# NewPowerandPlaceSCH.net
KiCad netlist of a schematic drawn in Altium Designer
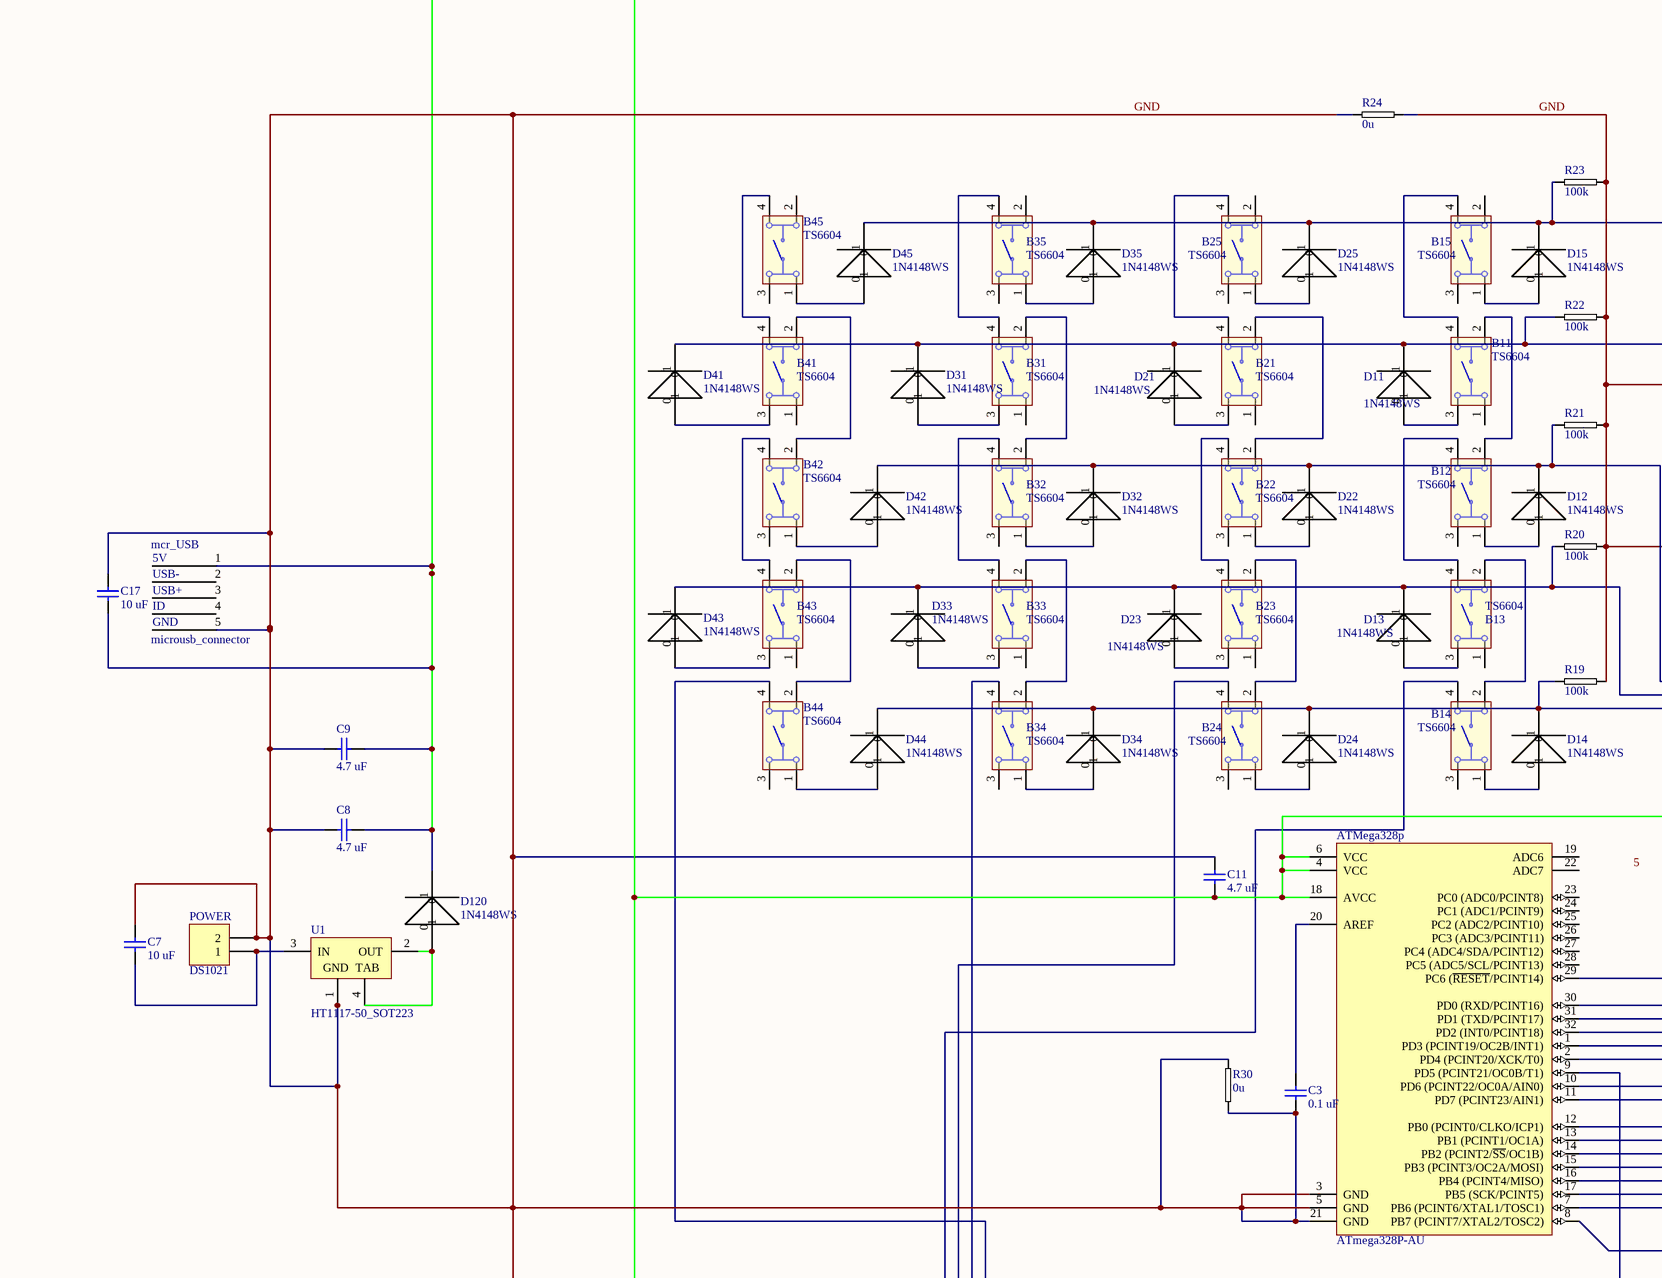
[diagram p0: NewPowerandPlaceSCH.SchDoc, top left]
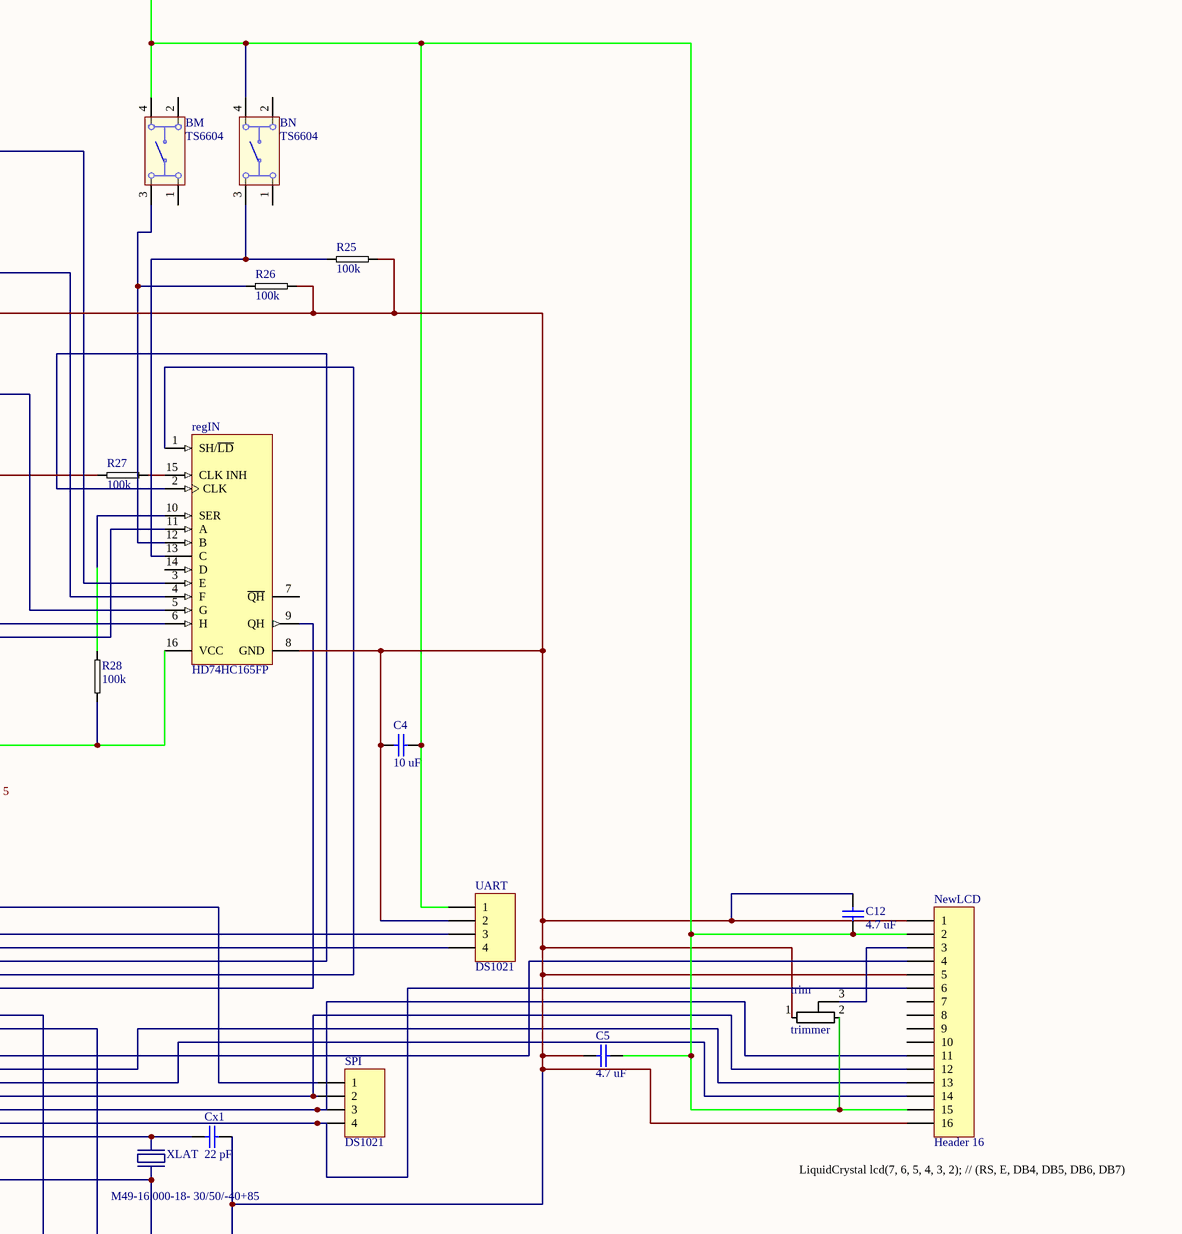
[diagram p1: NewPowerandPlaceSCH.SchDoc, top right]
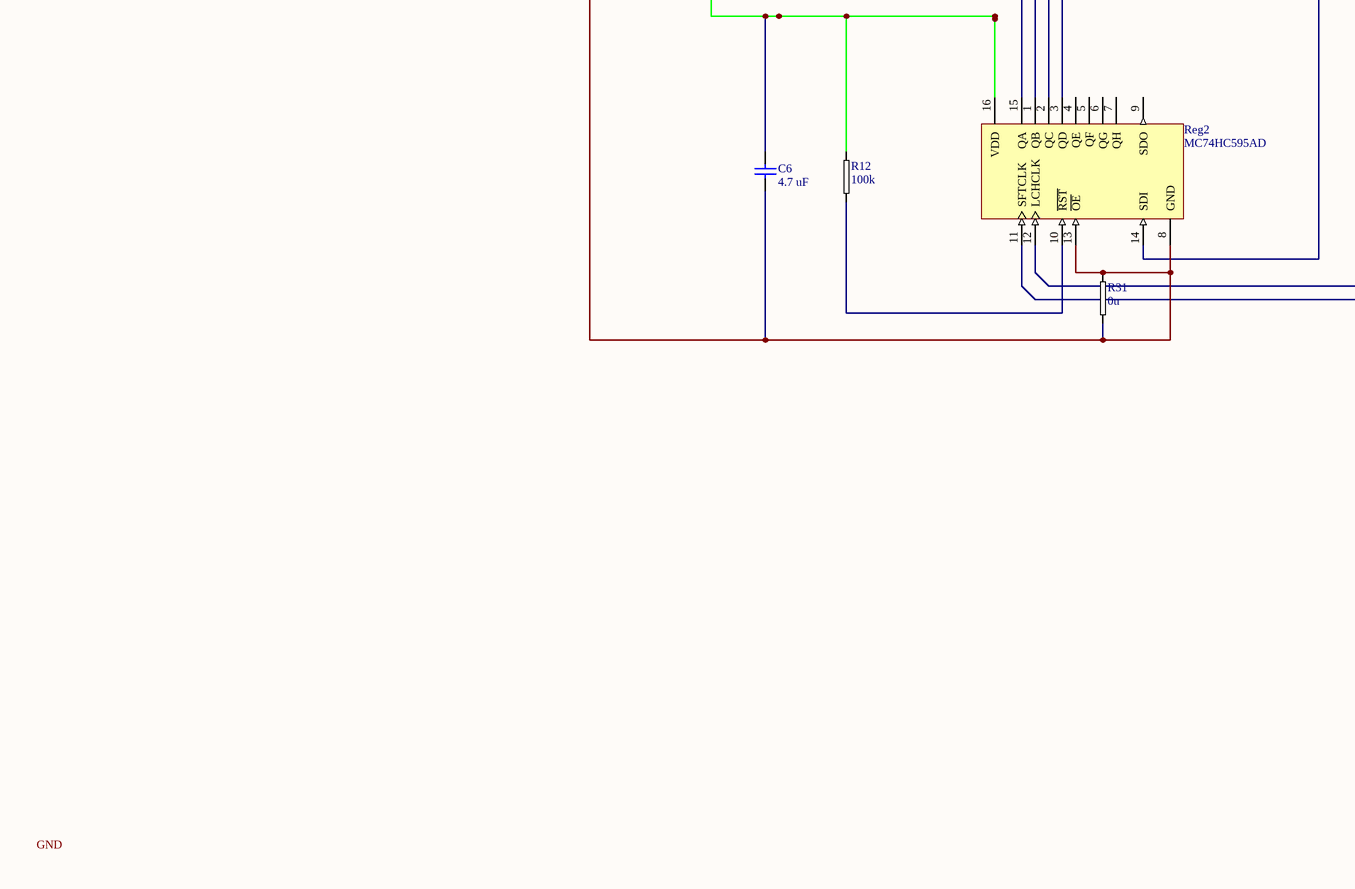
[diagram p2: NewPowerandPlaceSCH.SchDoc, bottom left]
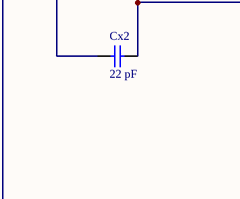
[diagram p3: NewPowerandPlaceSCH.SchDoc, bottom right]

(export (version "E")
  (design (tool "Eeschema 10.0.6"))
  (components
    (comp (ref "ATMega328p")
      (value "ATmega328P-AU")
      (footprint "32A_N")
      (libsource (lib "Atmel Microcontroller megaAVR") (part "ATmega328P-AU"))
    )
    (comp (ref "B11")
      (value "TS6604")
      (footprint "430182070816")
      (description "WS-TASV SMD Tact Switch 6X6 mm")
      (fields (field (name "PARTNUMBER") "430182070816"))
      (libsource (lib "WS-TASV SMD Tact Switch 6X6 mm") (part "430182070816"))
    )
    (comp (ref "B12")
      (value "TS6604")
      (footprint "430182070816")
      (description "WS-TASV SMD Tact Switch 6X6 mm")
      (fields (field (name "PARTNUMBER") "430182070816"))
      (libsource (lib "WS-TASV SMD Tact Switch 6X6 mm") (part "430182070816"))
    )
    (comp (ref "B13")
      (value "TS6604")
      (footprint "430182070816")
      (description "WS-TASV SMD Tact Switch 6X6 mm")
      (fields (field (name "PARTNUMBER") "430182070816"))
      (libsource (lib "WS-TASV SMD Tact Switch 6X6 mm") (part "430182070816"))
    )
    (comp (ref "B14")
      (value "TS6604")
      (footprint "430182070816")
      (description "WS-TASV SMD Tact Switch 6X6 mm")
      (fields (field (name "PARTNUMBER") "430182070816"))
      (libsource (lib "WS-TASV SMD Tact Switch 6X6 mm") (part "430182070816"))
    )
    (comp (ref "B15")
      (value "TS6604")
      (footprint "430182070816")
      (description "WS-TASV SMD Tact Switch 6X6 mm")
      (fields (field (name "PARTNUMBER") "430182070816"))
      (libsource (lib "WS-TASV SMD Tact Switch 6X6 mm") (part "430182070816"))
    )
    (comp (ref "B21")
      (value "TS6604")
      (footprint "430182070816")
      (description "WS-TASV SMD Tact Switch 6X6 mm")
      (fields (field (name "PARTNUMBER") "430182070816"))
      (libsource (lib "WS-TASV SMD Tact Switch 6X6 mm") (part "430182070816"))
    )
    (comp (ref "B22")
      (value "TS6604")
      (footprint "430182070816")
      (description "WS-TASV SMD Tact Switch 6X6 mm")
      (fields (field (name "PARTNUMBER") "430182070816"))
      (libsource (lib "WS-TASV SMD Tact Switch 6X6 mm") (part "430182070816"))
    )
    (comp (ref "B23")
      (value "TS6604")
      (footprint "430182070816")
      (description "WS-TASV SMD Tact Switch 6X6 mm")
      (fields (field (name "PARTNUMBER") "430182070816"))
      (libsource (lib "WS-TASV SMD Tact Switch 6X6 mm") (part "430182070816"))
    )
    (comp (ref "B24")
      (value "TS6604")
      (footprint "430182070816")
      (description "WS-TASV SMD Tact Switch 6X6 mm")
      (fields (field (name "PARTNUMBER") "430182070816"))
      (libsource (lib "WS-TASV SMD Tact Switch 6X6 mm") (part "430182070816"))
    )
    (comp (ref "B25")
      (value "TS6604")
      (footprint "430182070816")
      (description "WS-TASV SMD Tact Switch 6X6 mm")
      (fields (field (name "PARTNUMBER") "430182070816"))
      (libsource (lib "WS-TASV SMD Tact Switch 6X6 mm") (part "430182070816"))
    )
    (comp (ref "B31")
      (value "TS6604")
      (footprint "430182070816")
      (description "WS-TASV SMD Tact Switch 6X6 mm")
      (fields (field (name "PARTNUMBER") "430182070816"))
      (libsource (lib "WS-TASV SMD Tact Switch 6X6 mm") (part "430182070816"))
    )
    (comp (ref "B32")
      (value "TS6604")
      (footprint "430182070816")
      (description "WS-TASV SMD Tact Switch 6X6 mm")
      (fields (field (name "PARTNUMBER") "430182070816"))
      (libsource (lib "WS-TASV SMD Tact Switch 6X6 mm") (part "430182070816"))
    )
    (comp (ref "B33")
      (value "TS6604")
      (footprint "430182070816")
      (description "WS-TASV SMD Tact Switch 6X6 mm")
      (fields (field (name "PARTNUMBER") "430182070816"))
      (libsource (lib "WS-TASV SMD Tact Switch 6X6 mm") (part "430182070816"))
    )
    (comp (ref "B34")
      (value "TS6604")
      (footprint "430182070816")
      (description "WS-TASV SMD Tact Switch 6X6 mm")
      (fields (field (name "PARTNUMBER") "430182070816"))
      (libsource (lib "WS-TASV SMD Tact Switch 6X6 mm") (part "430182070816"))
    )
    (comp (ref "B35")
      (value "TS6604")
      (footprint "430182070816")
      (description "WS-TASV SMD Tact Switch 6X6 mm")
      (fields (field (name "PARTNUMBER") "430182070816"))
      (libsource (lib "WS-TASV SMD Tact Switch 6X6 mm") (part "430182070816"))
    )
    (comp (ref "B41")
      (value "TS6604")
      (footprint "430182070816")
      (description "WS-TASV SMD Tact Switch 6X6 mm")
      (fields (field (name "PARTNUMBER") "430182070816"))
      (libsource (lib "WS-TASV SMD Tact Switch 6X6 mm") (part "430182070816"))
    )
    (comp (ref "B42")
      (value "TS6604")
      (footprint "430182070816")
      (description "WS-TASV SMD Tact Switch 6X6 mm")
      (fields (field (name "PARTNUMBER") "430182070816"))
      (libsource (lib "WS-TASV SMD Tact Switch 6X6 mm") (part "430182070816"))
    )
    (comp (ref "B43")
      (value "TS6604")
      (footprint "430182070816")
      (description "WS-TASV SMD Tact Switch 6X6 mm")
      (fields (field (name "PARTNUMBER") "430182070816"))
      (libsource (lib "WS-TASV SMD Tact Switch 6X6 mm") (part "430182070816"))
    )
    (comp (ref "B44")
      (value "TS6604")
      (footprint "430182070816")
      (description "WS-TASV SMD Tact Switch 6X6 mm")
      (fields (field (name "PARTNUMBER") "430182070816"))
      (libsource (lib "WS-TASV SMD Tact Switch 6X6 mm") (part "430182070816"))
    )
    (comp (ref "B45")
      (value "TS6604")
      (footprint "430182070816")
      (description "WS-TASV SMD Tact Switch 6X6 mm")
      (fields (field (name "PARTNUMBER") "430182070816"))
      (libsource (lib "WS-TASV SMD Tact Switch 6X6 mm") (part "430182070816"))
    )
    (comp (ref "BM")
      (value "TS6604")
      (footprint "430182070816")
      (description "WS-TASV SMD Tact Switch 6X6 mm")
      (fields (field (name "PARTNUMBER") "430182070816"))
      (libsource (lib "WS-TASV SMD Tact Switch 6X6 mm") (part "430182070816"))
    )
    (comp (ref "BN")
      (value "TS6604")
      (footprint "430182070816")
      (description "WS-TASV SMD Tact Switch 6X6 mm")
      (fields (field (name "PARTNUMBER") "430182070816"))
      (libsource (lib "WS-TASV SMD Tact Switch 6X6 mm") (part "430182070816"))
    )
    (comp (ref "C3")
      (value "0.1 uF")
      (footprint "0805")
      (description "Ceramic Chip Capacitor - Standard")
      (fields (field (name "PUBLISHER") "Altium Limited"))
      (libsource (lib "KEMET Chip Capacitor") (part "C0805"))
    )
    (comp (ref "C11")
      (value "4.7 uF")
      (footprint "0805")
      (description "Ceramic Chip Capacitor - Standard")
      (fields (field (name "PUBLISHER") "Altium Limited"))
      (libsource (lib "KEMET Chip Capacitor") (part "C0805"))
    )
    (comp (ref "C12")
      (value "4.7 uF")
      (footprint "0805")
      (description "Ceramic Chip Capacitor - Standard")
      (fields (field (name "PUBLISHER") "Altium Limited"))
      (libsource (lib "KEMET Chip Capacitor") (part "C0805"))
    )
    (comp (ref "C17")
      (value "10 uF")
      (footprint "0805")
      (description "Ceramic Chip Capacitor - Standard")
      (fields (field (name "PUBLISHER") "Altium Limited"))
      (libsource (lib "KEMET Chip Capacitor") (part "C0805"))
    )
    (comp (ref "D11") (value "1N4148WS") (footprint "abak:sod323") (libsource (lib "abak") (part "SOD323")))
    (comp (ref "D12") (value "1N4148WS") (footprint "abak:sod323") (libsource (lib "abak") (part "SOD323")))
    (comp (ref "D13") (value "1N4148WS") (footprint "abak:sod323") (libsource (lib "abak") (part "SOD323")))
    (comp (ref "D14") (value "1N4148WS") (footprint "abak:sod323") (libsource (lib "abak") (part "SOD323")))
    (comp (ref "D15") (value "1N4148WS") (footprint "abak:sod323") (libsource (lib "abak") (part "SOD323")))
    (comp (ref "D21") (value "1N4148WS") (footprint "abak:sod323") (libsource (lib "abak") (part "SOD323")))
    (comp (ref "D22") (value "1N4148WS") (footprint "abak:sod323") (libsource (lib "abak") (part "SOD323")))
    (comp (ref "D23") (value "1N4148WS") (footprint "abak:sod323") (libsource (lib "abak") (part "SOD323")))
    (comp (ref "D24") (value "1N4148WS") (footprint "abak:sod323") (libsource (lib "abak") (part "SOD323")))
    (comp (ref "D25") (value "1N4148WS") (footprint "abak:sod323") (libsource (lib "abak") (part "SOD323")))
    (comp (ref "D31") (value "1N4148WS") (footprint "abak:sod323") (libsource (lib "abak") (part "SOD323")))
    (comp (ref "D32") (value "1N4148WS") (footprint "abak:sod323") (libsource (lib "abak") (part "SOD323")))
    (comp (ref "D33") (value "1N4148WS") (footprint "abak:sod323") (libsource (lib "abak") (part "SOD323")))
    (comp (ref "D34") (value "1N4148WS") (footprint "abak:sod323") (libsource (lib "abak") (part "SOD323")))
    (comp (ref "D35") (value "1N4148WS") (footprint "abak:sod323") (libsource (lib "abak") (part "SOD323")))
    (comp (ref "D41") (value "1N4148WS") (footprint "abak:sod323") (libsource (lib "abak") (part "SOD323")))
    (comp (ref "D42") (value "1N4148WS") (footprint "abak:sod323") (libsource (lib "abak") (part "SOD323")))
    (comp (ref "D43") (value "1N4148WS") (footprint "abak:sod323") (libsource (lib "abak") (part "SOD323")))
    (comp (ref "D44") (value "1N4148WS") (footprint "abak:sod323") (libsource (lib "abak") (part "SOD323")))
    (comp (ref "D45") (value "1N4148WS") (footprint "abak:sod323") (libsource (lib "abak") (part "SOD323")))
    (comp (ref "D120") (value "1N4148WS") (footprint "abak:sod323") (libsource (lib "abak") (part "SOD323")))
    (comp (ref "mcr_USB")
      (value "microusb_connector")
      (footprint "USB_connector_2")
      (libsource (lib "abak") (part "microusb_connector"))
    )
    (comp (ref "NewLCD")
      (value "Header 16")
      (footprint "HDR1X16")
      (description "Header, 16-Pin")
      (fields (field (name "PUBLISHER") "Altium Limited"))
      (libsource (lib "Miscellaneous Connectors") (part "Header 16"))
    )
    (comp (ref "POWER")
      (value "DS1021")
      (footprint "HDR1X2")
      (description "Header, 2-Pin")
      (fields (field (name "PUBLISHER") "Altium Limited"))
      (libsource (lib "Miscellaneous Connectors") (part "Header 2"))
    )
    (comp (ref "R12") (value "100k") (footprint "res_0805") (libsource (lib "") (part "res_0805_1")))
    (comp (ref "R19") (value "100k") (footprint "res_0805") (libsource (lib "res") (part "res_0805")))
    (comp (ref "R20") (value "100k") (footprint "res_0805") (libsource (lib "res") (part "res_0805")))
    (comp (ref "R21") (value "100k") (footprint "res_0805") (libsource (lib "res") (part "res_0805")))
    (comp (ref "R22") (value "100k") (footprint "res_0805") (libsource (lib "res") (part "res_0805")))
    (comp (ref "R23") (value "100k") (footprint "res_0805") (libsource (lib "res") (part "res_0805")))
    (comp (ref "R24") (value "0u") (footprint "res_0805") (libsource (lib "res") (part "res_0805")))
    (comp (ref "R25") (value "100k") (footprint "res_0805") (libsource (lib "res") (part "res_0805")))
    (comp (ref "R26") (value "100k") (footprint "res_0805") (libsource (lib "res") (part "res_0805")))
    (comp (ref "R27") (value "100k") (footprint "res_0805") (libsource (lib "res") (part "res_0805")))
    (comp (ref "R28") (value "100k") (footprint "res_0805") (libsource (lib "") (part "res_0805_1")))
    (comp (ref "R30") (value "0u") (footprint "res_0805") (libsource (lib "") (part "res_0805_1")))
    (comp (ref "R31") (value "0u") (footprint "res_0805") (libsource (lib "") (part "res_0805_1")))
    (comp (ref "Reg2")
      (value "MC74HC595AD")
      (footprint "751B-05_N")
      (description "8-Bit Serial-Input/Serial or Prallel-Output Shift Register with Latched 3-State Outputs")
      (fields (field (name "PUBLISHER") "Altium Limited"))
      (libsource (lib "ON Semi Logic Register") (part "MC74HC595AD"))
    )
    (comp (ref "regIN")
      (value "HD74HC165FP")
      (footprint "PRSP0016DH-B_N")
      (description "Parallel-Load 8-bit Shift Register")
      (fields (field (name "PUBLISHER") "Altium Limited"))
      (libsource (lib "Renesas Logic") (part "HD74HC165FP"))
    )
    (comp (ref "SPI")
      (value "DS1021")
      (footprint "HDR1X4")
      (description "Header, 4-Pin")
      (fields (field (name "PUBLISHER") "Altium Limited"))
      (libsource (lib "Miscellaneous Connectors") (part "Header 4"))
    )
    (comp (ref "trim")
      (value "trimmer")
      (footprint "trimmer_place")
      (libsource (lib "abak") (part "trimmer"))
    )
    (comp (ref "U1")
      (value "HT1117-50_SOT223")
      (footprint "SOT223_N")
      (description "5.0V, 1A General Purpose LDO")
      (libsource (lib "Holtek Semiconductor Power Management") (part "HT1117-50_SOT223"))
    )
    (comp (ref "UART")
      (value "DS1021")
      (footprint "HDR1X4")
      (description "Header, 4-Pin")
      (fields (field (name "PUBLISHER") "Altium Limited"))
      (libsource (lib "Miscellaneous Connectors") (part "Header 4"))
    )
    (comp (ref "XLAT")
      (value "M49-16.000-18- 30/50/-40+85")
      (footprint "cristal")
      (libsource (lib "abak") (part "cristal_smd"))
    )
    (comp (ref "С4")
      (value "10 uF")
      (footprint "0805")
      (description "Ceramic Chip Capacitor - Standard")
      (fields (field (name "PUBLISHER") "Altium Limited"))
      (libsource (lib "KEMET Chip Capacitor") (part "C0805"))
    )
    (comp (ref "С5")
      (value "4.7 uF")
      (footprint "0805")
      (description "Ceramic Chip Capacitor - Standard")
      (fields (field (name "PUBLISHER") "Altium Limited"))
      (libsource (lib "KEMET Chip Capacitor") (part "C0805"))
    )
    (comp (ref "С6")
      (value "4.7 uF")
      (footprint "0805")
      (description "Ceramic Chip Capacitor - Standard")
      (fields (field (name "PUBLISHER") "Altium Limited"))
      (libsource (lib "KEMET Chip Capacitor") (part "C0805"))
    )
    (comp (ref "С7")
      (value "10 uF")
      (footprint "0805")
      (description "Ceramic Chip Capacitor - Standard")
      (fields (field (name "PUBLISHER") "Altium Limited"))
      (libsource (lib "KEMET Chip Capacitor") (part "C0805"))
    )
    (comp (ref "С8")
      (value "4.7 uF")
      (footprint "0805")
      (description "Ceramic Chip Capacitor - Standard")
      (fields (field (name "PUBLISHER") "Altium Limited"))
      (libsource (lib "KEMET Chip Capacitor") (part "C0805"))
    )
    (comp (ref "С9")
      (value "4.7 uF")
      (footprint "0805")
      (description "Ceramic Chip Capacitor - Standard")
      (fields (field (name "PUBLISHER") "Altium Limited"))
      (libsource (lib "KEMET Chip Capacitor") (part "C0805"))
    )
    (comp (ref "Сx1")
      (value "22 pF")
      (footprint "res_0805")
      (description "Ceramic Chip Capacitor - Standard")
      (fields (field (name "PUBLISHER") "Altium Limited"))
      (libsource (lib "") (part "C0805_1"))
    )
    (comp (ref "Сx2")
      (value "22 pF")
      (footprint "res_0805")
      (description "Ceramic Chip Capacitor - Standard")
      (fields (field (name "PUBLISHER") "Altium Limited"))
      (libsource (lib "") (part "C0805_1"))
    )
  )
  (nets
    (net (code "2") (name "/GND") (class "Default")
      (node (ref "ATMega328p") (pin "21") (pinfunction "GND_21") (pintype "power_in"))
      (node (ref "ATMega328p") (pin "3") (pinfunction "GND_3") (pintype "power_in"))
      (node (ref "ATMega328p") (pin "5") (pinfunction "GND_5") (pintype "power_in"))
      (node (ref "C11") (pin "1") (pinfunction "1_1") (pintype "passive"))
      (node (ref "C12") (pin "2") (pinfunction "2_2") (pintype "passive"))
      (node (ref "C17") (pin "1") (pinfunction "1_1") (pintype "passive"))
      (node (ref "C3") (pin "2") (pinfunction "2_2") (pintype "passive"))
      (node (ref "NewLCD") (pin "1") (pinfunction "1_1") (pintype "passive"))
      (node (ref "NewLCD") (pin "16") (pinfunction "16_16") (pintype "passive"))
      (node (ref "NewLCD") (pin "5") (pinfunction "5_5") (pintype "passive"))
      (node (ref "POWER") (pin "2") (pinfunction "2_2") (pintype "passive"))
      (node (ref "R19") (pin "1") (pintype "passive"))
      (node (ref "R20") (pin "1") (pintype "passive"))
      (node (ref "R21") (pin "1") (pintype "passive"))
      (node (ref "R22") (pin "1") (pintype "passive"))
      (node (ref "R23") (pin "1") (pintype "passive"))
      (node (ref "R24") (pin "0") (pintype "passive"))
      (node (ref "R24") (pin "1") (pintype "passive"))
      (node (ref "R25") (pin "1") (pintype "passive"))
      (node (ref "R26") (pin "1") (pintype "passive"))
      (node (ref "R27") (pin "0") (pintype "passive"))
      (node (ref "R30") (pin "0") (pintype "passive"))
      (node (ref "R30") (pin "1") (pintype "passive"))
      (node (ref "R31") (pin "0") (pintype "passive"))
      (node (ref "R31") (pin "1") (pintype "passive"))
      (node (ref "Reg2") (pin "13") (pinfunction "~{OE}_13") (pintype "input"))
      (node (ref "Reg2") (pin "8") (pinfunction "GND_8") (pintype "power_in"))
      (node (ref "U1") (pin "1") (pinfunction "GND_1") (pintype "power_in"))
      (node (ref "UART") (pin "2") (pinfunction "2_2") (pintype "passive"))
      (node (ref "mcr_USB") (pin "5") (pintype "passive"))
      (node (ref "regIN") (pin "8") (pinfunction "GND_8") (pintype "power_in"))
      (node (ref "trim") (pin "1") (pintype "passive"))
      (node (ref "С4") (pin "1") (pinfunction "1_1") (pintype "passive"))
      (node (ref "С5") (pin "1") (pinfunction "1_1") (pintype "passive"))
      (node (ref "С6") (pin "2") (pinfunction "2_2") (pintype "passive"))
      (node (ref "С7") (pin "1") (pinfunction "1_1") (pintype "passive"))
      (node (ref "С8") (pin "1") (pinfunction "1_1") (pintype "passive"))
      (node (ref "С9") (pin "1") (pinfunction "1_1") (pintype "passive"))
      (node (ref "Сx1") (pin "1") (pinfunction "2_1") (pintype "passive"))
      (node (ref "Сx2") (pin "1") (pinfunction "2_1") (pintype "passive"))
    )
    (net (code "3") (name "Net-(ATMega328p-AREF)") (class "Default")
      (node (ref "ATMega328p") (pin "20") (pinfunction "AREF_20") (pintype "passive"))
      (node (ref "C3") (pin "1") (pinfunction "1_1") (pintype "passive"))
    )
    (net (code "4") (name "Net-(ATMega328p-AVCC)") (class "Default")
      (node (ref "ATMega328p") (pin "18") (pinfunction "AVCC_18") (pintype "power_in"))
      (node (ref "ATMega328p") (pin "4") (pinfunction "VCC_4") (pintype "power_in"))
      (node (ref "ATMega328p") (pin "6") (pinfunction "VCC_6") (pintype "power_in"))
      (node (ref "BM") (pin "4") (pinfunction "4_4") (pintype "passive"))
      (node (ref "BN") (pin "4") (pinfunction "4_4") (pintype "passive"))
      (node (ref "C11") (pin "2") (pinfunction "2_2") (pintype "passive"))
      (node (ref "C12") (pin "1") (pinfunction "1_1") (pintype "passive"))
      (node (ref "C17") (pin "2") (pinfunction "2_2") (pintype "passive"))
      (node (ref "D120") (pin "1") (pinfunction "1_1") (pintype "passive"))
      (node (ref "NewLCD") (pin "15") (pinfunction "15_15") (pintype "passive"))
      (node (ref "NewLCD") (pin "2") (pinfunction "2_2") (pintype "passive"))
      (node (ref "R12") (pin "1") (pintype "passive"))
      (node (ref "R28") (pin "0") (pintype "passive"))
      (node (ref "Reg2") (pin "16") (pinfunction "VDD_16") (pintype "power_in"))
      (node (ref "UART") (pin "1") (pinfunction "1_1") (pintype "passive"))
      (node (ref "mcr_USB") (pin "1") (pintype "passive"))
      (node (ref "regIN") (pin "16") (pinfunction "VCC_16") (pintype "power_in"))
      (node (ref "trim") (pin "2") (pintype "passive"))
      (node (ref "С4") (pin "2") (pinfunction "2_2") (pintype "passive"))
      (node (ref "С5") (pin "2") (pinfunction "2_2") (pintype "passive"))
      (node (ref "С6") (pin "1") (pinfunction "1_1") (pintype "passive"))
      (node (ref "С8") (pin "2") (pinfunction "2_2") (pintype "passive"))
      (node (ref "С9") (pin "2") (pinfunction "2_2") (pintype "passive"))
    )
    (net (code "5") (name "Net-(ATMega328p-PB0_(PCINT0{slash}CLKO{slash}ICP1))") (class "Default")
      (node (ref "ATMega328p") (pin "12") (pinfunction "PB0_(PCINT0/CLKO/ICP1)_12") (pintype "bidirectional"))
      (node (ref "NewLCD") (pin "4") (pinfunction "4_4") (pintype "passive"))
    )
    (net (code "6") (name "Net-(ATMega328p-PB1_(PCINT1{slash}OC1A))") (class "Default")
      (node (ref "ATMega328p") (pin "13") (pinfunction "PB1_(PCINT1/OC1A)_13") (pintype "bidirectional"))
      (node (ref "NewLCD") (pin "13") (pinfunction "13_13") (pintype "passive"))
    )
    (net (code "7") (name "Net-(ATMega328p-PB2_(PCINT2{slash}~{SS}{slash}OC1B))") (class "Default")
      (node (ref "ATMega328p") (pin "14") (pinfunction "PB2_(PCINT2/~{SS}/OC1B)_14") (pintype "bidirectional"))
      (node (ref "NewLCD") (pin "14") (pinfunction "14_14") (pintype "passive"))
    )
    (net (code "8") (name "Net-(ATMega328p-PB3_(PCINT3{slash}OC2A{slash}MOSI))") (class "Default")
      (node (ref "ATMega328p") (pin "15") (pinfunction "PB3_(PCINT3/OC2A/MOSI)_15") (pintype "bidirectional"))
      (node (ref "NewLCD") (pin "12") (pinfunction "12_12") (pintype "passive"))
      (node (ref "SPI") (pin "2") (pinfunction "2_2") (pintype "passive"))
    )
    (net (code "9") (name "Net-(ATMega328p-PB4_(PCINT4{slash}MISO))") (class "Default")
      (node (ref "ATMega328p") (pin "16") (pinfunction "PB4_(PCINT4/MISO)_16") (pintype "bidirectional"))
      (node (ref "NewLCD") (pin "11") (pinfunction "11_11") (pintype "passive"))
      (node (ref "SPI") (pin "3") (pinfunction "3_3") (pintype "passive"))
    )
    (net (code "10") (name "Net-(ATMega328p-PB5_(SCK{slash}PCINT5))") (class "Default")
      (node (ref "ATMega328p") (pin "17") (pinfunction "PB5_(SCK/PCINT5)_17") (pintype "bidirectional"))
      (node (ref "NewLCD") (pin "6") (pinfunction "6_6") (pintype "passive"))
      (node (ref "SPI") (pin "4") (pinfunction "4_4") (pintype "passive"))
    )
    (net (code "11") (name "Net-(ATMega328p-PB6_(PCINT6{slash}XTAL1{slash}TOSC1))") (class "Default")
      (node (ref "ATMega328p") (pin "7") (pinfunction "PB6_(PCINT6/XTAL1/TOSC1)_7") (pintype "bidirectional"))
      (node (ref "XLAT") (pin "1") (pintype "passive"))
      (node (ref "Сx1") (pin "0") (pinfunction "1_0") (pintype "passive"))
    )
    (net (code "12") (name "Net-(ATMega328p-PB7_(PCINT7{slash}XTAL2{slash}TOSC2))") (class "Default")
      (node (ref "ATMega328p") (pin "8") (pinfunction "PB7_(PCINT7/XTAL2/TOSC2)_8") (pintype "bidirectional"))
      (node (ref "XLAT") (pin "0") (pintype "passive"))
      (node (ref "Сx2") (pin "0") (pinfunction "1_0") (pintype "passive"))
    )
    (net (code "13") (name "Net-(ATMega328p-PC6_(~{RESET}{slash}PCINT14))") (class "Default")
      (node (ref "ATMega328p") (pin "29") (pinfunction "PC6_(~{RESET}/PCINT14)_29") (pintype "bidirectional"))
      (node (ref "SPI") (pin "1") (pinfunction "1_1") (pintype "passive"))
    )
    (net (code "14") (name "Net-(ATMega328p-PD0_(RXD{slash}PCINT16))") (class "Default")
      (node (ref "ATMega328p") (pin "30") (pinfunction "PD0_(RXD/PCINT16)_30") (pintype "bidirectional"))
      (node (ref "UART") (pin "3") (pinfunction "3_3") (pintype "passive"))
    )
    (net (code "15") (name "Net-(ATMega328p-PD1_(TXD{slash}PCINT17))") (class "Default")
      (node (ref "ATMega328p") (pin "31") (pinfunction "PD1_(TXD/PCINT17)_31") (pintype "bidirectional"))
      (node (ref "UART") (pin "4") (pinfunction "4_4") (pintype "passive"))
    )
    (net (code "16") (name "Net-(ATMega328p-PD2_(INT0{slash}PCINT18))") (class "Default")
      (node (ref "ATMega328p") (pin "32") (pinfunction "PD2_(INT0/PCINT18)_32") (pintype "bidirectional"))
      (node (ref "regIN") (pin "2") (pinfunction "CLK_2") (pintype "input"))
    )
    (net (code "17") (name "Net-(ATMega328p-PD3_(PCINT19{slash}OC2B{slash}INT1))") (class "Default")
      (node (ref "ATMega328p") (pin "1") (pinfunction "PD3_(PCINT19/OC2B/INT1)_1") (pintype "bidirectional"))
      (node (ref "regIN") (pin "1") (pinfunction "SH/~{LD}_1") (pintype "input"))
    )
    (net (code "18") (name "Net-(ATMega328p-PD4_(PCINT20{slash}XCK{slash}T0))") (class "Default")
      (node (ref "ATMega328p") (pin "2") (pinfunction "PD4_(PCINT20/XCK/T0)_2") (pintype "bidirectional"))
      (node (ref "regIN") (pin "9") (pinfunction "QH_9") (pintype "output"))
    )
    (net (code "19") (name "Net-(ATMega328p-PD5_(PCINT21{slash}OC0B{slash}T1))") (class "Default")
      (node (ref "ATMega328p") (pin "9") (pinfunction "PD5_(PCINT21/OC0B/T1)_9") (pintype "bidirectional"))
      (node (ref "Reg2") (pin "14") (pinfunction "SDI_14") (pintype "input"))
    )
    (net (code "20") (name "Net-(ATMega328p-PD6_(PCINT22{slash}OC0A{slash}AIN0))") (class "Default")
      (node (ref "ATMega328p") (pin "10") (pinfunction "PD6_(PCINT22/OC0A/AIN0)_10") (pintype "bidirectional"))
      (node (ref "Reg2") (pin "12") (pinfunction "LCHCLK_12") (pintype "input"))
    )
    (net (code "21") (name "Net-(ATMega328p-PD7_(PCINT23{slash}AIN1))") (class "Default")
      (node (ref "ATMega328p") (pin "11") (pinfunction "PD7_(PCINT23/AIN1)_11") (pintype "bidirectional"))
      (node (ref "Reg2") (pin "11") (pinfunction "SFTCLK_11") (pintype "input"))
    )
    (net (code "22") (name "Net-(B11-Pad2)") (class "Default")
      (node (ref "B11") (pin "2") (pinfunction "2_2") (pintype "passive"))
      (node (ref "B12") (pin "2") (pinfunction "2_2") (pintype "passive"))
    )
    (net (code "23") (name "Net-(B11-Pad3)") (class "Default")
      (node (ref "B11") (pin "3") (pinfunction "3_3") (pintype "passive"))
      (node (ref "D11") (pin "0") (pinfunction "0_0") (pintype "passive"))
    )
    (net (code "24") (name "Net-(B11-Pad4)") (class "Default")
      (node (ref "B11") (pin "4") (pinfunction "4_4") (pintype "passive"))
      (node (ref "B15") (pin "4") (pinfunction "4_4") (pintype "passive"))
    )
    (net (code "25") (name "Net-(B12-Pad1)") (class "Default")
      (node (ref "B12") (pin "1") (pinfunction "1_1") (pintype "passive"))
      (node (ref "D12") (pin "0") (pinfunction "0_0") (pintype "passive"))
    )
    (net (code "26") (name "Net-(B12-Pad4)") (class "Default")
      (node (ref "B12") (pin "4") (pinfunction "4_4") (pintype "passive"))
      (node (ref "B13") (pin "4") (pinfunction "4_4") (pintype "passive"))
    )
    (net (code "27") (name "Net-(B13-Pad2)") (class "Default")
      (node (ref "B13") (pin "2") (pinfunction "2_2") (pintype "passive"))
      (node (ref "B14") (pin "2") (pinfunction "2_2") (pintype "passive"))
    )
    (net (code "28") (name "Net-(B13-Pad3)") (class "Default")
      (node (ref "B13") (pin "3") (pinfunction "3_3") (pintype "passive"))
      (node (ref "D13") (pin "0") (pinfunction "0_0") (pintype "passive"))
    )
    (net (code "29") (name "Net-(B14-Pad1)") (class "Default")
      (node (ref "B14") (pin "1") (pinfunction "1_1") (pintype "passive"))
      (node (ref "D14") (pin "0") (pinfunction "0_0") (pintype "passive"))
    )
    (net (code "30") (name "Net-(B15-Pad1)") (class "Default")
      (node (ref "B15") (pin "1") (pinfunction "1_1") (pintype "passive"))
      (node (ref "D15") (pin "0") (pinfunction "0_0") (pintype "passive"))
    )
    (net (code "31") (name "Net-(B21-Pad2)") (class "Default")
      (node (ref "B21") (pin "2") (pinfunction "2_2") (pintype "passive"))
      (node (ref "B22") (pin "2") (pinfunction "2_2") (pintype "passive"))
    )
    (net (code "32") (name "Net-(B21-Pad3)") (class "Default")
      (node (ref "B21") (pin "3") (pinfunction "3_3") (pintype "passive"))
      (node (ref "D21") (pin "0") (pinfunction "0_0") (pintype "passive"))
    )
    (net (code "33") (name "Net-(B21-Pad4)") (class "Default")
      (node (ref "B21") (pin "4") (pinfunction "4_4") (pintype "passive"))
      (node (ref "B25") (pin "4") (pinfunction "4_4") (pintype "passive"))
    )
    (net (code "34") (name "Net-(B22-Pad1)") (class "Default")
      (node (ref "B22") (pin "1") (pinfunction "1_1") (pintype "passive"))
      (node (ref "D22") (pin "0") (pinfunction "0_0") (pintype "passive"))
    )
    (net (code "35") (name "Net-(B22-Pad4)") (class "Default")
      (node (ref "B22") (pin "4") (pinfunction "4_4") (pintype "passive"))
      (node (ref "B23") (pin "4") (pinfunction "4_4") (pintype "passive"))
    )
    (net (code "36") (name "Net-(B23-Pad2)") (class "Default")
      (node (ref "B23") (pin "2") (pinfunction "2_2") (pintype "passive"))
      (node (ref "B24") (pin "2") (pinfunction "2_2") (pintype "passive"))
    )
    (net (code "37") (name "Net-(B23-Pad3)") (class "Default")
      (node (ref "B23") (pin "3") (pinfunction "3_3") (pintype "passive"))
      (node (ref "D23") (pin "0") (pinfunction "0_0") (pintype "passive"))
    )
    (net (code "38") (name "Net-(B24-Pad1)") (class "Default")
      (node (ref "B24") (pin "1") (pinfunction "1_1") (pintype "passive"))
      (node (ref "D24") (pin "0") (pinfunction "0_0") (pintype "passive"))
    )
    (net (code "39") (name "Net-(B25-Pad1)") (class "Default")
      (node (ref "B25") (pin "1") (pinfunction "1_1") (pintype "passive"))
      (node (ref "D25") (pin "0") (pinfunction "0_0") (pintype "passive"))
    )
    (net (code "40") (name "Net-(B31-Pad2)") (class "Default")
      (node (ref "B31") (pin "2") (pinfunction "2_2") (pintype "passive"))
      (node (ref "B32") (pin "2") (pinfunction "2_2") (pintype "passive"))
    )
    (net (code "41") (name "Net-(B31-Pad3)") (class "Default")
      (node (ref "B31") (pin "3") (pinfunction "3_3") (pintype "passive"))
      (node (ref "D31") (pin "0") (pinfunction "0_0") (pintype "passive"))
    )
    (net (code "42") (name "Net-(B31-Pad4)") (class "Default")
      (node (ref "B31") (pin "4") (pinfunction "4_4") (pintype "passive"))
      (node (ref "B35") (pin "4") (pinfunction "4_4") (pintype "passive"))
    )
    (net (code "43") (name "Net-(B32-Pad1)") (class "Default")
      (node (ref "B32") (pin "1") (pinfunction "1_1") (pintype "passive"))
      (node (ref "D32") (pin "0") (pinfunction "0_0") (pintype "passive"))
    )
    (net (code "44") (name "Net-(B32-Pad4)") (class "Default")
      (node (ref "B32") (pin "4") (pinfunction "4_4") (pintype "passive"))
      (node (ref "B33") (pin "4") (pinfunction "4_4") (pintype "passive"))
    )
    (net (code "45") (name "Net-(B33-Pad2)") (class "Default")
      (node (ref "B33") (pin "2") (pinfunction "2_2") (pintype "passive"))
      (node (ref "B34") (pin "2") (pinfunction "2_2") (pintype "passive"))
    )
    (net (code "46") (name "Net-(B33-Pad3)") (class "Default")
      (node (ref "B33") (pin "3") (pinfunction "3_3") (pintype "passive"))
      (node (ref "D33") (pin "0") (pinfunction "0_0") (pintype "passive"))
    )
    (net (code "47") (name "Net-(B34-Pad1)") (class "Default")
      (node (ref "B34") (pin "1") (pinfunction "1_1") (pintype "passive"))
      (node (ref "D34") (pin "0") (pinfunction "0_0") (pintype "passive"))
    )
    (net (code "48") (name "Net-(B35-Pad1)") (class "Default")
      (node (ref "B35") (pin "1") (pinfunction "1_1") (pintype "passive"))
      (node (ref "D35") (pin "0") (pinfunction "0_0") (pintype "passive"))
    )
    (net (code "49") (name "Net-(B41-Pad2)") (class "Default")
      (node (ref "B41") (pin "2") (pinfunction "2_2") (pintype "passive"))
      (node (ref "B42") (pin "2") (pinfunction "2_2") (pintype "passive"))
    )
    (net (code "50") (name "Net-(B41-Pad3)") (class "Default")
      (node (ref "B41") (pin "3") (pinfunction "3_3") (pintype "passive"))
      (node (ref "D41") (pin "0") (pinfunction "0_0") (pintype "passive"))
    )
    (net (code "51") (name "Net-(B41-Pad4)") (class "Default")
      (node (ref "B41") (pin "4") (pinfunction "4_4") (pintype "passive"))
      (node (ref "B45") (pin "4") (pinfunction "4_4") (pintype "passive"))
    )
    (net (code "52") (name "Net-(B42-Pad1)") (class "Default")
      (node (ref "B42") (pin "1") (pinfunction "1_1") (pintype "passive"))
      (node (ref "D42") (pin "0") (pinfunction "0_0") (pintype "passive"))
    )
    (net (code "53") (name "Net-(B42-Pad4)") (class "Default")
      (node (ref "B42") (pin "4") (pinfunction "4_4") (pintype "passive"))
      (node (ref "B43") (pin "4") (pinfunction "4_4") (pintype "passive"))
    )
    (net (code "54") (name "Net-(B43-Pad2)") (class "Default")
      (node (ref "B43") (pin "2") (pinfunction "2_2") (pintype "passive"))
      (node (ref "B44") (pin "2") (pinfunction "2_2") (pintype "passive"))
    )
    (net (code "55") (name "Net-(B43-Pad3)") (class "Default")
      (node (ref "B43") (pin "3") (pinfunction "3_3") (pintype "passive"))
      (node (ref "D43") (pin "0") (pinfunction "0_0") (pintype "passive"))
    )
    (net (code "56") (name "Net-(B44-Pad1)") (class "Default")
      (node (ref "B44") (pin "1") (pinfunction "1_1") (pintype "passive"))
      (node (ref "D44") (pin "0") (pinfunction "0_0") (pintype "passive"))
    )
    (net (code "57") (name "Net-(B45-Pad1)") (class "Default")
      (node (ref "B45") (pin "1") (pinfunction "1_1") (pintype "passive"))
      (node (ref "D45") (pin "0") (pinfunction "0_0") (pintype "passive"))
    )
    (net (code "58") (name "Net-(NewLCD-Pad3)") (class "Default")
      (node (ref "NewLCD") (pin "3") (pinfunction "3_3") (pintype "passive"))
      (node (ref "trim") (pin "3") (pintype "passive"))
    )
    (net (code "59") (name "Net-(Reg2-QA)") (class "Default")
      (node (ref "B14") (pin "4") (pinfunction "4_4") (pintype "passive"))
      (node (ref "Reg2") (pin "15") (pinfunction "QA_15") (pintype "tri_state"))
    )
    (net (code "60") (name "Net-(Reg2-QB)") (class "Default")
      (node (ref "B24") (pin "4") (pinfunction "4_4") (pintype "passive"))
      (node (ref "Reg2") (pin "1") (pinfunction "QB_1") (pintype "tri_state"))
    )
    (net (code "61") (name "Net-(Reg2-QC)") (class "Default")
      (node (ref "B34") (pin "4") (pinfunction "4_4") (pintype "passive"))
      (node (ref "Reg2") (pin "2") (pinfunction "QC_2") (pintype "tri_state"))
    )
    (net (code "62") (name "Net-(Reg2-QD)") (class "Default")
      (node (ref "B44") (pin "4") (pinfunction "4_4") (pintype "passive"))
      (node (ref "Reg2") (pin "3") (pinfunction "QD_3") (pintype "tri_state"))
    )
    (net (code "63") (name "Net-(Reg2-~{RST})") (class "Default")
      (node (ref "R12") (pin "0") (pintype "passive"))
      (node (ref "Reg2") (pin "10") (pinfunction "~{RST}_10") (pintype "input"))
    )
    (net (code "64") (name "Net-(U1-IN)") (class "Default")
      (node (ref "POWER") (pin "1") (pinfunction "1_1") (pintype "passive"))
      (node (ref "U1") (pin "3") (pinfunction "IN_3") (pintype "power_in"))
      (node (ref "С7") (pin "2") (pinfunction "2_2") (pintype "passive"))
    )
    (net (code "65") (name "Net-(U1-OUT)") (class "Default")
      (node (ref "D120") (pin "0") (pinfunction "0_0") (pintype "passive"))
      (node (ref "U1") (pin "2") (pinfunction "OUT_2") (pintype "power_in"))
      (node (ref "U1") (pin "4") (pinfunction "TAB_4") (pintype "power_in"))
    )
    (net (code "66") (name "Net-(regIN-A)") (class "Default")
      (node (ref "D14") (pin "1") (pinfunction "1_1") (pintype "passive"))
      (node (ref "D24") (pin "1") (pinfunction "1_1") (pintype "passive"))
      (node (ref "D34") (pin "1") (pinfunction "1_1") (pintype "passive"))
      (node (ref "D44") (pin "1") (pinfunction "1_1") (pintype "passive"))
      (node (ref "R19") (pin "0") (pintype "passive"))
      (node (ref "regIN") (pin "11") (pinfunction "A_11") (pintype "input"))
    )
    (net (code "67") (name "Net-(regIN-B)") (class "Default")
      (node (ref "BM") (pin "3") (pinfunction "3_3") (pintype "passive"))
      (node (ref "R26") (pin "0") (pintype "passive"))
      (node (ref "regIN") (pin "12") (pinfunction "B_12") (pintype "input"))
    )
    (net (code "68") (name "Net-(regIN-C)") (class "Default")
      (node (ref "BN") (pin "3") (pinfunction "3_3") (pintype "passive"))
      (node (ref "R25") (pin "0") (pintype "passive"))
      (node (ref "regIN") (pin "13") (pinfunction "C_13") (pintype "passive"))
    )
    (net (code "69") (name "Net-(regIN-CLK_INH)") (class "Default")
      (node (ref "R27") (pin "1") (pintype "passive"))
      (node (ref "regIN") (pin "15") (pinfunction "CLK_INH_15") (pintype "input"))
    )
    (net (code "70") (name "Net-(regIN-E)") (class "Default")
      (node (ref "D15") (pin "1") (pinfunction "1_1") (pintype "passive"))
      (node (ref "D25") (pin "1") (pinfunction "1_1") (pintype "passive"))
      (node (ref "D35") (pin "1") (pinfunction "1_1") (pintype "passive"))
      (node (ref "D45") (pin "1") (pinfunction "1_1") (pintype "passive"))
      (node (ref "R23") (pin "0") (pintype "passive"))
      (node (ref "regIN") (pin "3") (pinfunction "E_3") (pintype "input"))
    )
    (net (code "71") (name "Net-(regIN-F)") (class "Default")
      (node (ref "D11") (pin "1") (pinfunction "1_1") (pintype "passive"))
      (node (ref "D21") (pin "1") (pinfunction "1_1") (pintype "passive"))
      (node (ref "D31") (pin "1") (pinfunction "1_1") (pintype "passive"))
      (node (ref "D41") (pin "1") (pinfunction "1_1") (pintype "passive"))
      (node (ref "R22") (pin "0") (pintype "passive"))
      (node (ref "regIN") (pin "4") (pinfunction "F_4") (pintype "input"))
    )
    (net (code "72") (name "Net-(regIN-G)") (class "Default")
      (node (ref "D12") (pin "1") (pinfunction "1_1") (pintype "passive"))
      (node (ref "D22") (pin "1") (pinfunction "1_1") (pintype "passive"))
      (node (ref "D32") (pin "1") (pinfunction "1_1") (pintype "passive"))
      (node (ref "D42") (pin "1") (pinfunction "1_1") (pintype "passive"))
      (node (ref "R21") (pin "0") (pintype "passive"))
      (node (ref "regIN") (pin "5") (pinfunction "G_5") (pintype "input"))
    )
    (net (code "73") (name "Net-(regIN-H)") (class "Default")
      (node (ref "D13") (pin "1") (pinfunction "1_1") (pintype "passive"))
      (node (ref "D23") (pin "1") (pinfunction "1_1") (pintype "passive"))
      (node (ref "D33") (pin "1") (pinfunction "1_1") (pintype "passive"))
      (node (ref "D43") (pin "1") (pinfunction "1_1") (pintype "passive"))
      (node (ref "R20") (pin "0") (pintype "passive"))
      (node (ref "regIN") (pin "6") (pinfunction "H_6") (pintype "input"))
    )
    (net (code "74") (name "Net-(regIN-SER)") (class "Default")
      (node (ref "R28") (pin "1") (pintype "passive"))
      (node (ref "regIN") (pin "10") (pinfunction "SER_10") (pintype "input"))
    )
    (net (code "75") (name "unconnected-(ATMega328p-ADC6-Pad19)") (class "Default")
      (node (ref "ATMega328p") (pin "19") (pinfunction "ADC6_19") (pintype "passive"))
    )
    (net (code "76") (name "unconnected-(ATMega328p-ADC7-Pad22)") (class "Default")
      (node (ref "ATMega328p") (pin "22") (pinfunction "ADC7_22") (pintype "passive"))
    )
    (net (code "77") (name "unconnected-(ATMega328p-PC0_(ADC0{slash}PCINT8)-Pad23)") (class "Default")
      (node (ref "ATMega328p") (pin "23") (pinfunction "PC0_(ADC0/PCINT8)_23") (pintype "bidirectional"))
    )
    (net (code "78") (name "unconnected-(ATMega328p-PC1_(ADC1{slash}PCINT9)-Pad24)") (class "Default")
      (node (ref "ATMega328p") (pin "24") (pinfunction "PC1_(ADC1/PCINT9)_24") (pintype "bidirectional"))
    )
    (net (code "79") (name "unconnected-(ATMega328p-PC2_(ADC2{slash}PCINT10)-Pad25)") (class "Default")
      (node (ref "ATMega328p") (pin "25") (pinfunction "PC2_(ADC2/PCINT10)_25") (pintype "bidirectional"))
    )
    (net (code "80") (name "unconnected-(ATMega328p-PC3_(ADC3{slash}PCINT11)-Pad26)") (class "Default")
      (node (ref "ATMega328p") (pin "26") (pinfunction "PC3_(ADC3/PCINT11)_26") (pintype "bidirectional"))
    )
    (net (code "81") (name "unconnected-(ATMega328p-PC4_(ADC4{slash}SDA{slash}PCINT12)-Pad27)") (class "Default")
      (node (ref "ATMega328p") (pin "27") (pinfunction "PC4_(ADC4/SDA/PCINT12)_27") (pintype "bidirectional"))
    )
    (net (code "82") (name "unconnected-(ATMega328p-PC5_(ADC5{slash}SCL{slash}PCINT13)-Pad28)") (class "Default")
      (node (ref "ATMega328p") (pin "28") (pinfunction "PC5_(ADC5/SCL/PCINT13)_28") (pintype "bidirectional"))
    )
    (net (code "83") (name "unconnected-(B11-Pad1)") (class "Default")
      (node (ref "B11") (pin "1") (pinfunction "1_1") (pintype "passive"))
    )
    (net (code "84") (name "unconnected-(B12-Pad3)") (class "Default")
      (node (ref "B12") (pin "3") (pinfunction "3_3") (pintype "passive"))
    )
    (net (code "85") (name "unconnected-(B13-Pad1)") (class "Default")
      (node (ref "B13") (pin "1") (pinfunction "1_1") (pintype "passive"))
    )
    (net (code "86") (name "unconnected-(B14-Pad3)") (class "Default")
      (node (ref "B14") (pin "3") (pinfunction "3_3") (pintype "passive"))
    )
    (net (code "87") (name "unconnected-(B15-Pad2)") (class "Default")
      (node (ref "B15") (pin "2") (pinfunction "2_2") (pintype "passive"))
    )
    (net (code "88") (name "unconnected-(B15-Pad3)") (class "Default")
      (node (ref "B15") (pin "3") (pinfunction "3_3") (pintype "passive"))
    )
    (net (code "89") (name "unconnected-(B21-Pad1)") (class "Default")
      (node (ref "B21") (pin "1") (pinfunction "1_1") (pintype "passive"))
    )
    (net (code "90") (name "unconnected-(B22-Pad3)") (class "Default")
      (node (ref "B22") (pin "3") (pinfunction "3_3") (pintype "passive"))
    )
    (net (code "91") (name "unconnected-(B23-Pad1)") (class "Default")
      (node (ref "B23") (pin "1") (pinfunction "1_1") (pintype "passive"))
    )
    (net (code "92") (name "unconnected-(B24-Pad3)") (class "Default")
      (node (ref "B24") (pin "3") (pinfunction "3_3") (pintype "passive"))
    )
    (net (code "93") (name "unconnected-(B25-Pad2)") (class "Default")
      (node (ref "B25") (pin "2") (pinfunction "2_2") (pintype "passive"))
    )
    (net (code "94") (name "unconnected-(B25-Pad3)") (class "Default")
      (node (ref "B25") (pin "3") (pinfunction "3_3") (pintype "passive"))
    )
    (net (code "95") (name "unconnected-(B31-Pad1)") (class "Default")
      (node (ref "B31") (pin "1") (pinfunction "1_1") (pintype "passive"))
    )
    (net (code "96") (name "unconnected-(B32-Pad3)") (class "Default")
      (node (ref "B32") (pin "3") (pinfunction "3_3") (pintype "passive"))
    )
    (net (code "97") (name "unconnected-(B33-Pad1)") (class "Default")
      (node (ref "B33") (pin "1") (pinfunction "1_1") (pintype "passive"))
    )
    (net (code "98") (name "unconnected-(B34-Pad3)") (class "Default")
      (node (ref "B34") (pin "3") (pinfunction "3_3") (pintype "passive"))
    )
    (net (code "99") (name "unconnected-(B35-Pad2)") (class "Default")
      (node (ref "B35") (pin "2") (pinfunction "2_2") (pintype "passive"))
    )
    (net (code "100") (name "unconnected-(B35-Pad3)") (class "Default")
      (node (ref "B35") (pin "3") (pinfunction "3_3") (pintype "passive"))
    )
    (net (code "101") (name "unconnected-(B41-Pad1)") (class "Default")
      (node (ref "B41") (pin "1") (pinfunction "1_1") (pintype "passive"))
    )
    (net (code "102") (name "unconnected-(B42-Pad3)") (class "Default")
      (node (ref "B42") (pin "3") (pinfunction "3_3") (pintype "passive"))
    )
    (net (code "103") (name "unconnected-(B43-Pad1)") (class "Default")
      (node (ref "B43") (pin "1") (pinfunction "1_1") (pintype "passive"))
    )
    (net (code "104") (name "unconnected-(B44-Pad3)") (class "Default")
      (node (ref "B44") (pin "3") (pinfunction "3_3") (pintype "passive"))
    )
    (net (code "105") (name "unconnected-(B45-Pad2)") (class "Default")
      (node (ref "B45") (pin "2") (pinfunction "2_2") (pintype "passive"))
    )
    (net (code "106") (name "unconnected-(B45-Pad3)") (class "Default")
      (node (ref "B45") (pin "3") (pinfunction "3_3") (pintype "passive"))
    )
    (net (code "107") (name "unconnected-(BM-Pad1)") (class "Default")
      (node (ref "BM") (pin "1") (pinfunction "1_1") (pintype "passive"))
    )
    (net (code "108") (name "unconnected-(BM-Pad2)") (class "Default")
      (node (ref "BM") (pin "2") (pinfunction "2_2") (pintype "passive"))
    )
    (net (code "109") (name "unconnected-(BN-Pad1)") (class "Default")
      (node (ref "BN") (pin "1") (pinfunction "1_1") (pintype "passive"))
    )
    (net (code "110") (name "unconnected-(BN-Pad2)") (class "Default")
      (node (ref "BN") (pin "2") (pinfunction "2_2") (pintype "passive"))
    )
    (net (code "111") (name "unconnected-(NewLCD-Pad7)") (class "Default")
      (node (ref "NewLCD") (pin "7") (pinfunction "7_7") (pintype "passive"))
    )
    (net (code "112") (name "unconnected-(NewLCD-Pad8)") (class "Default")
      (node (ref "NewLCD") (pin "8") (pinfunction "8_8") (pintype "passive"))
    )
    (net (code "113") (name "unconnected-(NewLCD-Pad9)") (class "Default")
      (node (ref "NewLCD") (pin "9") (pinfunction "9_9") (pintype "passive"))
    )
    (net (code "114") (name "unconnected-(NewLCD-Pad10)") (class "Default")
      (node (ref "NewLCD") (pin "10") (pinfunction "10_10") (pintype "passive"))
    )
    (net (code "115") (name "unconnected-(Reg2-QE-Pad4)") (class "Default")
      (node (ref "Reg2") (pin "4") (pinfunction "QE_4") (pintype "tri_state"))
    )
    (net (code "116") (name "unconnected-(Reg2-QF-Pad5)") (class "Default")
      (node (ref "Reg2") (pin "5") (pinfunction "QF_5") (pintype "tri_state"))
    )
    (net (code "117") (name "unconnected-(Reg2-QG-Pad6)") (class "Default")
      (node (ref "Reg2") (pin "6") (pinfunction "QG_6") (pintype "tri_state"))
    )
    (net (code "118") (name "unconnected-(Reg2-QH-Pad7)") (class "Default")
      (node (ref "Reg2") (pin "7") (pinfunction "QH_7") (pintype "tri_state"))
    )
    (net (code "119") (name "unconnected-(Reg2-SDO-Pad9)") (class "Default")
      (node (ref "Reg2") (pin "9") (pinfunction "SDO_9") (pintype "output"))
    )
    (net (code "120") (name "unconnected-(mcr_USB-Pad2)") (class "Default")
      (node (ref "mcr_USB") (pin "2") (pintype "passive"))
    )
    (net (code "121") (name "unconnected-(mcr_USB-Pad3)") (class "Default")
      (node (ref "mcr_USB") (pin "3") (pintype "passive"))
    )
    (net (code "122") (name "unconnected-(mcr_USB-Pad4)") (class "Default")
      (node (ref "mcr_USB") (pin "4") (pintype "passive"))
    )
    (net (code "123") (name "unconnected-(regIN-D-Pad14)") (class "Default")
      (node (ref "regIN") (pin "14") (pinfunction "D_14") (pintype "input"))
    )
    (net (code "124") (name "unconnected-(regIN-~{QH}-Pad7)") (class "Default")
      (node (ref "regIN") (pin "7") (pinfunction "~{QH}_7") (pintype "passive"))
    )
  )
)
